# USB_Phy.net
KiCad netlist of a schematic drawn in Altium Designer
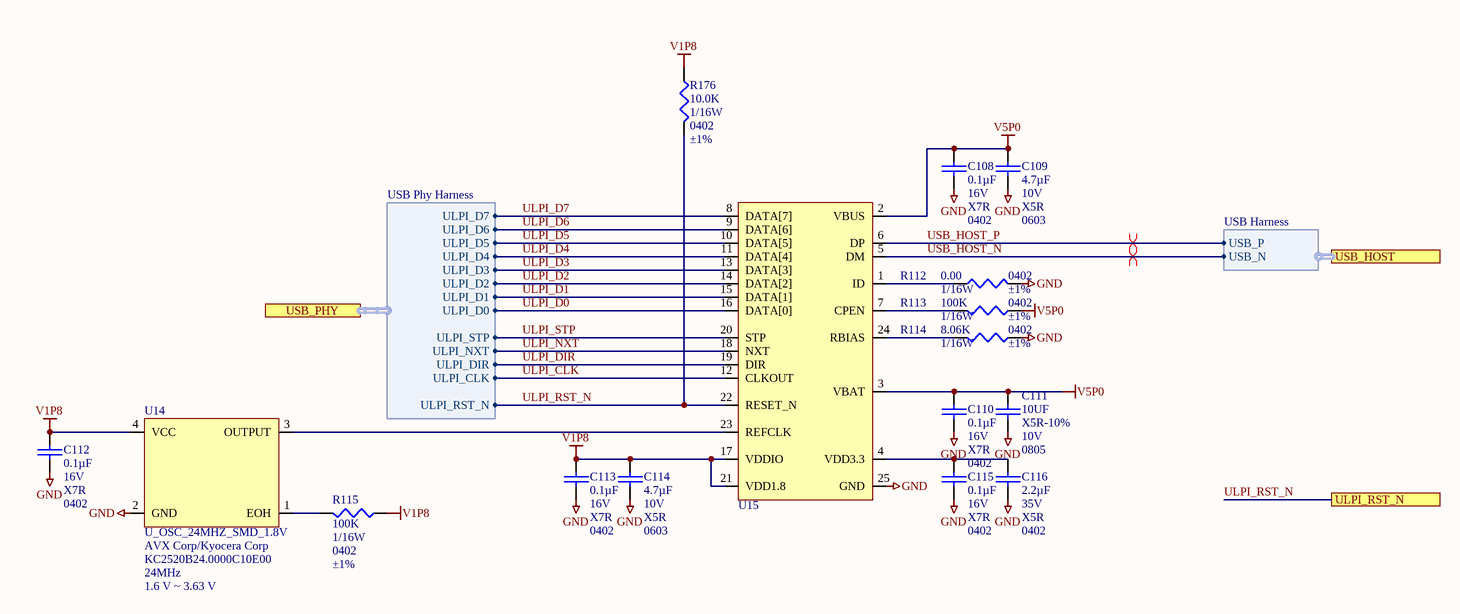
[diagram p0: USB Phy.SchDoc]

(export (version "E")
  (design (tool "Eeschema 10.0.6"))
  (components
    (comp (ref "C108")
      (value "0.1uF")
      (footprint "C_0402")
      (description "CAP CER .10UF 16V X7R 0402")
      (fields
        (field (name "MANUFACTURER") "Murata Electronics North America")
        (field (name "MANUFACTURER PART NUMBER") "GRM155R71C104KA88J")
        (field (name "CAPACITANCE") "0.1µF")
        (field (name "VOLTAGE - RATED") "16V")
        (field (name "TEMPERATURE COEFFICIENT") "X7R")
        (field (name "PACKAGE / CASE") "0402")
      )
      (libsource (lib "Main LibraryX") (part "C_0402_0.1UF_16V"))
    )
    (comp (ref "C109")
      (value "4.7µF")
      (footprint "C_ERA-0603")
      (description "CAP CER 4.7UF 10V X5R 0603")
      (fields
        (field (name "MANUFACTURER") "Murata Electronics North America")
        (field (name "MANUFACTURER PART NUMBER") "GRM188R61A475KE15D")
        (field (name "CAPACITANCE") "4.7µF")
        (field (name "VOLTAGE - RATED") "10V")
        (field (name "TEMPERATURE COEFFICIENT") "X5R")
        (field (name "PACKAGE / CASE") "0603")
      )
      (libsource (lib "Main LibraryX") (part "C_0603_4.7uF_10V"))
    )
    (comp (ref "C110")
      (value "0.1uF")
      (footprint "C_0402")
      (description "CAP CER .10UF 16V X7R 0402")
      (fields
        (field (name "MANUFACTURER") "Murata Electronics North America")
        (field (name "MANUFACTURER PART NUMBER") "GRM155R71C104KA88J")
        (field (name "CAPACITANCE") "0.1µF")
        (field (name "VOLTAGE - RATED") "16V")
        (field (name "TEMPERATURE COEFFICIENT") "X7R")
        (field (name "PACKAGE / CASE") "0402")
      )
      (libsource (lib "Main LibraryX") (part "C_0402_0.1UF_16V"))
    )
    (comp (ref "C111")
      (value "10UF")
      (footprint "0805")
      (description "CAP CER 10UF 10V 10% X5R 0805")
      (fields
        (field (name "MANUFACTURER") "Murata Electronics North America")
        (field (name "MANUFACTURER PART NUMBER") "GRM21BR61A106KE19L")
        (field (name "TOLERANCE") "X5R-10%")
        (field (name "VOLTS") "10V")
      )
      (libsource (lib "Main Library") (part "C_0805_10UF_10V"))
    )
    (comp (ref "C112")
      (value "0.1uF")
      (footprint "C_0402")
      (description "CAP CER .10UF 16V X7R 0402")
      (fields
        (field (name "MANUFACTURER") "Murata Electronics North America")
        (field (name "MANUFACTURER PART NUMBER") "GRM155R71C104KA88J")
        (field (name "CAPACITANCE") "0.1µF")
        (field (name "VOLTAGE - RATED") "16V")
        (field (name "TEMPERATURE COEFFICIENT") "X7R")
        (field (name "PACKAGE / CASE") "0402")
      )
      (libsource (lib "Main LibraryX") (part "C_0402_0.1UF_16V"))
    )
    (comp (ref "C113")
      (value "0.1uF")
      (footprint "C_0402")
      (description "CAP CER .10UF 16V X7R 0402")
      (fields
        (field (name "MANUFACTURER") "Murata Electronics North America")
        (field (name "MANUFACTURER PART NUMBER") "GRM155R71C104KA88J")
        (field (name "CAPACITANCE") "0.1µF")
        (field (name "VOLTAGE - RATED") "16V")
        (field (name "TEMPERATURE COEFFICIENT") "X7R")
        (field (name "PACKAGE / CASE") "0402")
      )
      (libsource (lib "Main LibraryX") (part "C_0402_0.1UF_16V"))
    )
    (comp (ref "C114")
      (value "4.7µF")
      (footprint "C_ERA-0603")
      (description "CAP CER 4.7UF 10V X5R 0603")
      (fields
        (field (name "MANUFACTURER") "Murata Electronics North America")
        (field (name "MANUFACTURER PART NUMBER") "GRM188R61A475KE15D")
        (field (name "CAPACITANCE") "4.7µF")
        (field (name "VOLTAGE - RATED") "10V")
        (field (name "TEMPERATURE COEFFICIENT") "X5R")
        (field (name "PACKAGE / CASE") "0603")
      )
      (libsource (lib "Main LibraryX") (part "C_0603_4.7uF_10V"))
    )
    (comp (ref "C115")
      (value "0.1uF")
      (footprint "C_0402")
      (description "CAP CER .10UF 16V X7R 0402")
      (fields
        (field (name "MANUFACTURER") "Murata Electronics North America")
        (field (name "MANUFACTURER PART NUMBER") "GRM155R71C104KA88J")
        (field (name "CAPACITANCE") "0.1µF")
        (field (name "VOLTAGE - RATED") "16V")
        (field (name "TEMPERATURE COEFFICIENT") "X7R")
        (field (name "PACKAGE / CASE") "0402")
      )
      (libsource (lib "Main LibraryX") (part "C_0402_0.1UF_16V"))
    )
    (comp (ref "C116")
      (value "C_0402_2.2uF_35V")
      (footprint "C_ERA-0402")
      (description "CAP CER 2.2UF 35V 20% X5R 0402")
      (fields
        (field (name "MANUFACTURER") "TDK Corporation")
        (field (name "MANUFACTURER PART NUMBER") "C1005X5R1V225K050BC")
        (field (name "CAPACITANCE") "2.2µF")
        (field (name "VOLTAGE - RATED") "35V")
        (field (name "TEMPERATURE COEFFICIENT") "X5R")
        (field (name "PACKAGE / CASE") "0402")
      )
      (libsource (lib "Main LibraryX") (part "C_0402_2.2uF_35V"))
    )
    (comp (ref "R112")
      (value "0.0 Ohms")
      (footprint "R_0402")
      (description "RES SMD 0.0OHM JUMPER 1/10W 0402")
      (fields
        (field (name "MANUFACTURER") "Panasonic - ECG")
        (field (name "MANUFACTURER PART NUMBER") "ERJ-2GE0R00X")
        (field (name "RESISTANCE IN OHMS") "0.00")
        (field (name "POWER (WATTS)") "1/16W")
        (field (name "CASE") "0402")
        (field (name "TOLERANCE") "±1%")
      )
      (libsource (lib "Main LibraryX") (part "R_0402_0.00"))
    )
    (comp (ref "R113")
      (value "R_0402_100K")
      (footprint "R_0402")
      (description "RES SMD 100K OHM 1% 1/16W 0402")
      (fields
        (field (name "MANUFACTURER") "Yageo")
        (field (name "MANUFACTURER PART NUMBER") "RC0402FR-07100KL")
        (field (name "RESISTANCE IN OHMS") "100K")
        (field (name "POWER (WATTS)") "1/16W")
        (field (name "CASE") "0402")
        (field (name "TOLERANCE") "±1%")
      )
      (libsource (lib "Cospan Design") (part "R_0402_100K"))
    )
    (comp (ref "R114")
      (value "R_0402_8.06K")
      (footprint "R_0402")
      (description "RES 8.06K OHM 1/16W 1% 0402 SMD")
      (fields
        (field (name "MANUFACTURER") "Yageo")
        (field (name "MANUFACTURER PART NUMBER") "RC0402FR-078K06L")
        (field (name "RESISTANCE IN OHMS") "8.06K")
        (field (name "POWER (WATTS)") "1/16W")
        (field (name "CASE") "0402")
        (field (name "TOLERANCE") "±1%")
      )
      (libsource (lib "Main Library") (part "R_0402_8.06K"))
    )
    (comp (ref "R115")
      (value "R_0402_100K")
      (footprint "R_0402")
      (description "RES SMD 100K OHM 1% 1/16W 0402")
      (fields
        (field (name "MANUFACTURER") "Yageo")
        (field (name "MANUFACTURER PART NUMBER") "RC0402FR-07100KL")
        (field (name "RESISTANCE IN OHMS") "100K")
        (field (name "POWER (WATTS)") "1/16W")
        (field (name "CASE") "0402")
        (field (name "TOLERANCE") "±1%")
      )
      (libsource (lib "Cospan Design") (part "R_0402_100K"))
    )
    (comp (ref "R176")
      (value "R_0402_10.0K")
      (footprint "R_0402")
      (description "RES 10.0K OHM 1/16W 1% 0402 SMD")
      (fields
        (field (name "MANUFACTURER") "Stackpole Electronics Inc")
        (field (name "MANUFACTURER PART NUMBER") "RMCF0402FT10K0")
        (field (name "RESISTANCE IN OHMS") "10.0K")
        (field (name "POWER (WATTS)") "1/16W")
        (field (name "CASE") "0402")
        (field (name "TOLERANCE") "±1%")
      )
      (libsource (lib "Main Library") (part "R_0402_10.0K"))
    )
    (comp (ref "U14")
      (value "U_OSC_24MHZ_SMD_1.8V")
      (footprint "KC2520B")
      (description "24MHz CMOS XO (Standard) Oscillator")
      (fields
        (field (name "MANUFACTURER") "AVX Corp/Kyocera Corp")
        (field (name "MANUFACTURER PART NUMBER") "KC2520B24.0000C10E00")
        (field (name "FREQUENCY") "24MHz")
        (field (name "VOLTAGE - SUPPLY") "1.6 V ~ 3.63 V")
      )
      (libsource (lib "Cospan Design") (part "U_OSC_24MHZ_SMD_1.8V"))
    )
    (comp (ref "U15")
      (value "U_USB3315C")
      (footprint "QFN50P400X400X100_HS-25N")
      (description "IC TXRX USB FLEXPWR 24QFN")
      (fields
        (field (name "MANUFACTURER") "Microchip Technology")
        (field (name "MANUFACTURER PART NUMBER") "USB3315C-CP-TR")
      )
      (libsource (lib "Cospan Design") (part "U_USB3315C"))
    )
  )
  (nets
    (net (code "4") (name "/ULPI_CLK") (class "Default")
      (node (ref "U15") (pin "12") (pinfunction "CLKOUT_12") (pintype "passive"))
    )
    (net (code "5") (name "/ULPI_D0") (class "Default")
      (node (ref "U15") (pin "16") (pinfunction "DATA[0]_16") (pintype "passive"))
    )
    (net (code "6") (name "/ULPI_D1") (class "Default")
      (node (ref "U15") (pin "15") (pinfunction "DATA[1]_15") (pintype "passive"))
    )
    (net (code "7") (name "/ULPI_D2") (class "Default")
      (node (ref "U15") (pin "14") (pinfunction "DATA[2]_14") (pintype "passive"))
    )
    (net (code "8") (name "/ULPI_D3") (class "Default")
      (node (ref "U15") (pin "13") (pinfunction "DATA[3]_13") (pintype "passive"))
    )
    (net (code "9") (name "/ULPI_D4") (class "Default")
      (node (ref "U15") (pin "11") (pinfunction "DATA[4]_11") (pintype "passive"))
    )
    (net (code "10") (name "/ULPI_D5") (class "Default")
      (node (ref "U15") (pin "10") (pinfunction "DATA[5]_10") (pintype "passive"))
    )
    (net (code "11") (name "/ULPI_D6") (class "Default")
      (node (ref "U15") (pin "9") (pinfunction "DATA[6]_9") (pintype "passive"))
    )
    (net (code "12") (name "/ULPI_D7") (class "Default")
      (node (ref "U15") (pin "8") (pinfunction "DATA[7]_8") (pintype "passive"))
    )
    (net (code "13") (name "/ULPI_DIR") (class "Default")
      (node (ref "U15") (pin "19") (pinfunction "DIR_19") (pintype "passive"))
    )
    (net (code "14") (name "/ULPI_NXT") (class "Default")
      (node (ref "U15") (pin "18") (pinfunction "NXT_18") (pintype "passive"))
    )
    (net (code "15") (name "/ULPI_RST_N") (class "Default")
      (node (ref "R176") (pin "1") (pinfunction "1_1") (pintype "passive"))
      (node (ref "U15") (pin "22") (pinfunction "RESET_N_22") (pintype "passive"))
    )
    (net (code "16") (name "/ULPI_STP") (class "Default")
      (node (ref "U15") (pin "20") (pinfunction "STP_20") (pintype "passive"))
    )
    (net (code "17") (name "/USB_HOST_N") (class "Default")
      (node (ref "U15") (pin "5") (pinfunction "DM_5") (pintype "passive"))
    )
    (net (code "18") (name "/USB_HOST_P") (class "Default")
      (node (ref "U15") (pin "6") (pinfunction "DP_6") (pintype "passive"))
    )
    (net (code "21") (name "GND") (class "Default")
      (node (ref "C108") (pin "1") (pinfunction "1_1") (pintype "passive"))
      (node (ref "C109") (pin "1") (pinfunction "1_1") (pintype "passive"))
      (node (ref "C110") (pin "1") (pinfunction "1_1") (pintype "passive"))
      (node (ref "C111") (pin "1") (pinfunction "1_1") (pintype "passive"))
      (node (ref "C112") (pin "1") (pinfunction "1_1") (pintype "passive"))
      (node (ref "C113") (pin "1") (pinfunction "1_1") (pintype "passive"))
      (node (ref "C114") (pin "1") (pinfunction "1_1") (pintype "passive"))
      (node (ref "C115") (pin "1") (pinfunction "1_1") (pintype "passive"))
      (node (ref "C116") (pin "1") (pinfunction "1_1") (pintype "passive"))
      (node (ref "R112") (pin "1") (pinfunction "1_1") (pintype "passive"))
      (node (ref "R114") (pin "2") (pinfunction "2_2") (pintype "passive"))
      (node (ref "U14") (pin "2") (pinfunction "GND_2") (pintype "passive"))
      (node (ref "U15") (pin "25") (pinfunction "GND_25") (pintype "passive"))
    )
    (net (code "22") (name "Net-(U14-EOH)") (class "Default")
      (node (ref "R115") (pin "1") (pinfunction "1_1") (pintype "passive"))
      (node (ref "U14") (pin "1") (pinfunction "EOH_1") (pintype "passive"))
    )
    (net (code "23") (name "Net-(U14-OUTPUT)") (class "Default")
      (node (ref "U14") (pin "3") (pinfunction "OUTPUT_3") (pintype "passive"))
      (node (ref "U15") (pin "23") (pinfunction "REFCLK_23") (pintype "passive"))
    )
    (net (code "24") (name "Net-(U15-CPEN)") (class "Default")
      (node (ref "R113") (pin "1") (pinfunction "1_1") (pintype "passive"))
      (node (ref "U15") (pin "7") (pinfunction "CPEN_7") (pintype "passive"))
    )
    (net (code "25") (name "Net-(U15-ID)") (class "Default")
      (node (ref "R112") (pin "2") (pinfunction "2_2") (pintype "passive"))
      (node (ref "U15") (pin "1") (pinfunction "ID_1") (pintype "passive"))
    )
    (net (code "26") (name "Net-(U15-RBIAS)") (class "Default")
      (node (ref "R114") (pin "1") (pinfunction "1_1") (pintype "passive"))
      (node (ref "U15") (pin "24") (pinfunction "RBIAS_24") (pintype "passive"))
    )
    (net (code "27") (name "Net-(U15-VDD3.3)") (class "Default")
      (node (ref "C115") (pin "2") (pinfunction "2_2") (pintype "passive"))
      (node (ref "C116") (pin "2") (pinfunction "2_2") (pintype "passive"))
      (node (ref "U15") (pin "4") (pinfunction "VDD3.3_4") (pintype "passive"))
    )
    (net (code "28") (name "V1P8") (class "Default")
      (node (ref "C112") (pin "2") (pinfunction "2_2") (pintype "passive"))
      (node (ref "C113") (pin "2") (pinfunction "2_2") (pintype "passive"))
      (node (ref "C114") (pin "2") (pinfunction "2_2") (pintype "passive"))
      (node (ref "R115") (pin "2") (pinfunction "2_2") (pintype "passive"))
      (node (ref "R176") (pin "2") (pinfunction "2_2") (pintype "passive"))
      (node (ref "U14") (pin "4") (pinfunction "VCC_4") (pintype "passive"))
      (node (ref "U15") (pin "17") (pinfunction "VDDIO_17") (pintype "passive"))
      (node (ref "U15") (pin "21") (pinfunction "VDD1.8_21") (pintype "passive"))
    )
    (net (code "29") (name "V5P0") (class "Default")
      (node (ref "C108") (pin "2") (pinfunction "2_2") (pintype "passive"))
      (node (ref "C109") (pin "2") (pinfunction "2_2") (pintype "passive"))
      (node (ref "C110") (pin "2") (pinfunction "2_2") (pintype "passive"))
      (node (ref "C111") (pin "2") (pinfunction "2_2") (pintype "passive"))
      (node (ref "R113") (pin "2") (pinfunction "2_2") (pintype "passive"))
      (node (ref "U15") (pin "2") (pinfunction "VBUS_2") (pintype "passive"))
      (node (ref "U15") (pin "3") (pinfunction "VBAT_3") (pintype "passive"))
    )
  )
)
